# FFC-STDC14-adapter.net
KiCad netlist of a schematic drawn in Altium Designer
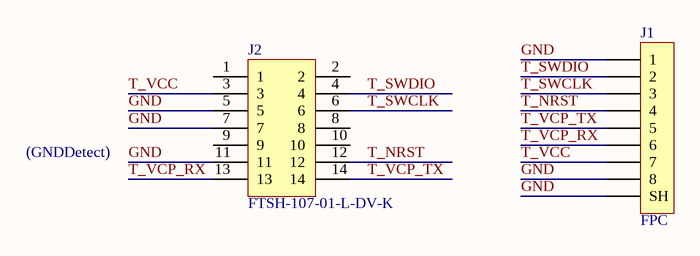
[diagram p0: FFC-STDC14-adapter.SchDoc]

(export (version "E")
  (design (tool "Eeschema 10.0.6"))
  (components
    (comp (ref "J1")
      (value "FPC")
      (footprint "HIROSE-FH19C-8S-0.5SH")
      (libsource (lib "connectors") (part "FPC-CONNECTOR-8"))
    )
    (comp (ref "J2")
      (value "FTSH-107-01-L-DV-K")
      (footprint "FTSH-107-01-L-DV-K")
      (libsource (lib "connectors") (part "FTSH-107-01-L-DV-K"))
    )
  )
  (nets
    (net (code "1") (name "/GND") (class "Default")
      (node (ref "J1") (pin "1") (pinfunction "1_1") (pintype "passive"))
      (node (ref "J1") (pin "8") (pinfunction "8_8") (pintype "passive"))
      (node (ref "J1") (pin "SH") (pinfunction "SH_SH") (pintype "passive"))
      (node (ref "J2") (pin "11") (pinfunction "11_11") (pintype "passive"))
      (node (ref "J2") (pin "5") (pinfunction "5_5") (pintype "passive"))
      (node (ref "J2") (pin "7") (pinfunction "7_7") (pintype "passive"))
    )
    (net (code "2") (name "/T_NRST") (class "Default")
      (node (ref "J1") (pin "4") (pinfunction "4_4") (pintype "passive"))
      (node (ref "J2") (pin "12") (pinfunction "12_12") (pintype "passive"))
    )
    (net (code "3") (name "/T_SWCLK") (class "Default")
      (node (ref "J1") (pin "3") (pinfunction "3_3") (pintype "passive"))
      (node (ref "J2") (pin "6") (pinfunction "6_6") (pintype "passive"))
    )
    (net (code "4") (name "/T_SWDIO") (class "Default")
      (node (ref "J1") (pin "2") (pinfunction "2_2") (pintype "passive"))
      (node (ref "J2") (pin "4") (pinfunction "4_4") (pintype "passive"))
    )
    (net (code "5") (name "/T_VCC") (class "Default")
      (node (ref "J1") (pin "7") (pinfunction "7_7") (pintype "passive"))
      (node (ref "J2") (pin "3") (pinfunction "3_3") (pintype "passive"))
    )
    (net (code "6") (name "/T_VCP_RX") (class "Default")
      (node (ref "J1") (pin "6") (pinfunction "6_6") (pintype "passive"))
      (node (ref "J2") (pin "13") (pinfunction "13_13") (pintype "passive"))
    )
    (net (code "7") (name "/T_VCP_TX") (class "Default")
      (node (ref "J1") (pin "5") (pinfunction "5_5") (pintype "passive"))
      (node (ref "J2") (pin "14") (pinfunction "14_14") (pintype "passive"))
    )
    (net (code "8") (name "unconnected-(J2-Pad1)") (class "Default")
      (node (ref "J2") (pin "1") (pinfunction "1_1") (pintype "passive"))
    )
    (net (code "9") (name "unconnected-(J2-Pad2)") (class "Default")
      (node (ref "J2") (pin "2") (pinfunction "2_2") (pintype "passive"))
    )
    (net (code "10") (name "unconnected-(J2-Pad8)") (class "Default")
      (node (ref "J2") (pin "8") (pinfunction "8_8") (pintype "passive"))
    )
    (net (code "11") (name "unconnected-(J2-Pad9)") (class "Default")
      (node (ref "J2") (pin "9") (pinfunction "9_9") (pintype "passive"))
    )
    (net (code "12") (name "unconnected-(J2-Pad10)") (class "Default")
      (node (ref "J2") (pin "10") (pinfunction "10_10") (pintype "passive"))
    )
  )
)
